# ProTrinket_doubleHPdisplay.net
KiCad netlist of a schematic drawn in EAGLE
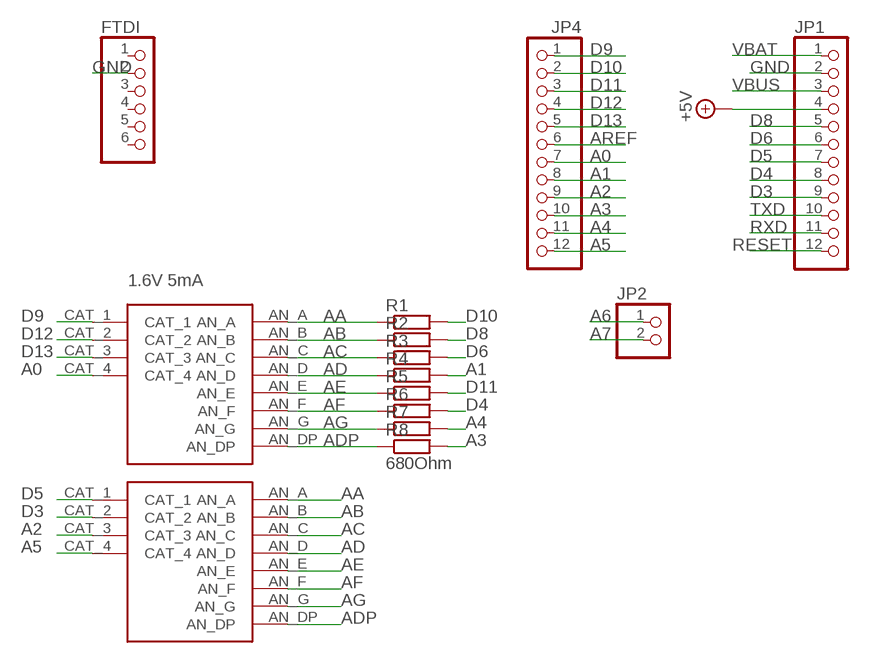
[diagram p0: schematic, sheet 1]

(export (version "E")
  (design (tool "Eeschema 10.0.6"))
  (components
    (comp (ref "FTDI")
      (value "PINHD-1X6CB")
      (footprint "eagle-import:1X06-CLEANBIG")
      (libsource (lib "eagle-import") (part "PINHD-1X6CB"))
    )
    (comp (ref "JP1")
      (value "PINHD-1X12-CB")
      (footprint "eagle-import:1X12-CB")
      (libsource (lib "eagle-import") (part "PINHD-1X12-CB"))
    )
    (comp (ref "JP2")
      (value "HEADER-1X2ROUND")
      (footprint "eagle-import:1X02_ROUND")
      (libsource (lib "eagle-import") (part "HEADER-1X2ROUND"))
    )
    (comp (ref "JP4")
      (value "PINHD-1X12-CB")
      (footprint "eagle-import:1X12-CB")
      (libsource (lib "eagle-import") (part "PINHD-1X12-CB"))
    )
    (comp (ref "R1")
      (value "R-EU_R0603")
      (footprint "eagle-import:R0603")
      (libsource (lib "eagle-import") (part "R-EU_R0603"))
    )
    (comp (ref "R2")
      (value "R-EU_R0603")
      (footprint "eagle-import:R0603")
      (libsource (lib "eagle-import") (part "R-EU_R0603"))
    )
    (comp (ref "R3")
      (value "R-EU_R0603")
      (footprint "eagle-import:R0603")
      (libsource (lib "eagle-import") (part "R-EU_R0603"))
    )
    (comp (ref "R4")
      (value "R-EU_R0603")
      (footprint "eagle-import:R0603")
      (libsource (lib "eagle-import") (part "R-EU_R0603"))
    )
    (comp (ref "R5")
      (value "R-EU_R0603")
      (footprint "eagle-import:R0603")
      (libsource (lib "eagle-import") (part "R-EU_R0603"))
    )
    (comp (ref "R6")
      (value "R-EU_R0603")
      (footprint "eagle-import:R0603")
      (libsource (lib "eagle-import") (part "R-EU_R0603"))
    )
    (comp (ref "R7")
      (value "R-EU_R0603")
      (footprint "eagle-import:R0603")
      (libsource (lib "eagle-import") (part "R-EU_R0603"))
    )
    (comp (ref "R8")
      (value "680Ohm")
      (footprint "eagle-import:R0603")
      (libsource (lib "eagle-import") (part "R-EU_R0603"))
    )
    (comp (ref "U$1")
      (value "QDSP-6064")
      (footprint "eagle-import:QDSP-6064")
      (libsource (lib "eagle-import") (part "QDSP-6064"))
    )
    (comp (ref "U$2")
      (value "QDSP-6064")
      (footprint "eagle-import:QDSP-6064")
      (libsource (lib "eagle-import") (part "QDSP-6064"))
    )
  )
  (nets
    (net (code "1") (name "+5V") (class "Default")
      (node (ref "JP1") (pin "4") (pinfunction "4_4") (pintype "passive"))
    )
    (net (code "2") (name "/A0") (class "Default")
      (node (ref "JP4") (pin "7") (pinfunction "7_7") (pintype "passive"))
      (node (ref "U$1") (pin "CAT_4") (pinfunction "CAT_4_CAT_4") (pintype "bidirectional"))
    )
    (net (code "3") (name "/A1") (class "Default")
      (node (ref "JP4") (pin "8") (pinfunction "8_8") (pintype "passive"))
      (node (ref "R4") (pin "2") (pinfunction "2_2") (pintype "passive"))
    )
    (net (code "4") (name "/A2") (class "Default")
      (node (ref "JP4") (pin "9") (pinfunction "9_9") (pintype "passive"))
      (node (ref "U$2") (pin "CAT_3") (pinfunction "CAT_3_CAT_3") (pintype "bidirectional"))
    )
    (net (code "5") (name "/A3") (class "Default")
      (node (ref "JP4") (pin "10") (pinfunction "10_10") (pintype "passive"))
      (node (ref "R8") (pin "2") (pinfunction "2_2") (pintype "passive"))
    )
    (net (code "6") (name "/A4") (class "Default")
      (node (ref "JP4") (pin "11") (pinfunction "11_11") (pintype "passive"))
      (node (ref "R7") (pin "2") (pinfunction "2_2") (pintype "passive"))
    )
    (net (code "7") (name "/A5") (class "Default")
      (node (ref "JP4") (pin "12") (pinfunction "12_12") (pintype "passive"))
      (node (ref "U$2") (pin "CAT_4") (pinfunction "CAT_4_CAT_4") (pintype "bidirectional"))
    )
    (net (code "8") (name "/A6") (class "Default")
      (node (ref "JP2") (pin "1") (pinfunction "1_1") (pintype "passive"))
    )
    (net (code "9") (name "/A7") (class "Default")
      (node (ref "JP2") (pin "2") (pinfunction "2_2") (pintype "passive"))
    )
    (net (code "10") (name "/AA") (class "Default")
      (node (ref "R1") (pin "1") (pinfunction "1_1") (pintype "passive"))
      (node (ref "U$1") (pin "AN_A") (pinfunction "AN_A_AN_A") (pintype "bidirectional"))
      (node (ref "U$2") (pin "AN_A") (pinfunction "AN_A_AN_A") (pintype "bidirectional"))
    )
    (net (code "11") (name "/AB") (class "Default")
      (node (ref "R2") (pin "1") (pinfunction "1_1") (pintype "passive"))
      (node (ref "U$1") (pin "AN_B") (pinfunction "AN_B_AN_B") (pintype "bidirectional"))
      (node (ref "U$2") (pin "AN_B") (pinfunction "AN_B_AN_B") (pintype "bidirectional"))
    )
    (net (code "12") (name "/AC") (class "Default")
      (node (ref "R3") (pin "1") (pinfunction "1_1") (pintype "passive"))
      (node (ref "U$1") (pin "AN_C") (pinfunction "AN_C_AN_C") (pintype "bidirectional"))
      (node (ref "U$2") (pin "AN_C") (pinfunction "AN_C_AN_C") (pintype "bidirectional"))
    )
    (net (code "13") (name "/AD") (class "Default")
      (node (ref "R4") (pin "1") (pinfunction "1_1") (pintype "passive"))
      (node (ref "U$1") (pin "AN_D") (pinfunction "AN_D_AN_D") (pintype "bidirectional"))
      (node (ref "U$2") (pin "AN_D") (pinfunction "AN_D_AN_D") (pintype "bidirectional"))
    )
    (net (code "14") (name "/ADP") (class "Default")
      (node (ref "R8") (pin "1") (pinfunction "1_1") (pintype "passive"))
      (node (ref "U$1") (pin "AN_DP") (pinfunction "AN_DP_AN_DP") (pintype "bidirectional"))
      (node (ref "U$2") (pin "AN_DP") (pinfunction "AN_DP_AN_DP") (pintype "bidirectional"))
    )
    (net (code "15") (name "/AE") (class "Default")
      (node (ref "R5") (pin "1") (pinfunction "1_1") (pintype "passive"))
      (node (ref "U$1") (pin "AN_E") (pinfunction "AN_E_AN_E") (pintype "bidirectional"))
      (node (ref "U$2") (pin "AN_E") (pinfunction "AN_E_AN_E") (pintype "bidirectional"))
    )
    (net (code "16") (name "/AF") (class "Default")
      (node (ref "R6") (pin "1") (pinfunction "1_1") (pintype "passive"))
      (node (ref "U$1") (pin "AN_F") (pinfunction "AN_F_AN_F") (pintype "bidirectional"))
      (node (ref "U$2") (pin "AN_F") (pinfunction "AN_F_AN_F") (pintype "bidirectional"))
    )
    (net (code "17") (name "/AG") (class "Default")
      (node (ref "R7") (pin "1") (pinfunction "1_1") (pintype "passive"))
      (node (ref "U$1") (pin "AN_G") (pinfunction "AN_G_AN_G") (pintype "bidirectional"))
      (node (ref "U$2") (pin "AN_G") (pinfunction "AN_G_AN_G") (pintype "bidirectional"))
    )
    (net (code "18") (name "/AREF") (class "Default")
      (node (ref "JP4") (pin "6") (pinfunction "6_6") (pintype "passive"))
    )
    (net (code "19") (name "/D3") (class "Default")
      (node (ref "JP1") (pin "9") (pinfunction "9_9") (pintype "passive"))
      (node (ref "U$2") (pin "CAT_2") (pinfunction "CAT_2_CAT_2") (pintype "bidirectional"))
    )
    (net (code "20") (name "/D4") (class "Default")
      (node (ref "JP1") (pin "8") (pinfunction "8_8") (pintype "passive"))
      (node (ref "R6") (pin "2") (pinfunction "2_2") (pintype "passive"))
    )
    (net (code "21") (name "/D5") (class "Default")
      (node (ref "JP1") (pin "7") (pinfunction "7_7") (pintype "passive"))
      (node (ref "U$2") (pin "CAT_1") (pinfunction "CAT_1_CAT_1") (pintype "bidirectional"))
    )
    (net (code "22") (name "/D6") (class "Default")
      (node (ref "JP1") (pin "6") (pinfunction "6_6") (pintype "passive"))
      (node (ref "R3") (pin "2") (pinfunction "2_2") (pintype "passive"))
    )
    (net (code "23") (name "/D8") (class "Default")
      (node (ref "JP1") (pin "5") (pinfunction "5_5") (pintype "passive"))
      (node (ref "R2") (pin "2") (pinfunction "2_2") (pintype "passive"))
    )
    (net (code "24") (name "/D9") (class "Default")
      (node (ref "JP4") (pin "1") (pinfunction "1_1") (pintype "passive"))
      (node (ref "U$1") (pin "CAT_1") (pinfunction "CAT_1_CAT_1") (pintype "bidirectional"))
    )
    (net (code "25") (name "/D10") (class "Default")
      (node (ref "JP4") (pin "2") (pinfunction "2_2") (pintype "passive"))
      (node (ref "R1") (pin "2") (pinfunction "2_2") (pintype "passive"))
    )
    (net (code "26") (name "/D11") (class "Default")
      (node (ref "JP4") (pin "3") (pinfunction "3_3") (pintype "passive"))
      (node (ref "R5") (pin "2") (pinfunction "2_2") (pintype "passive"))
    )
    (net (code "27") (name "/D12") (class "Default")
      (node (ref "JP4") (pin "4") (pinfunction "4_4") (pintype "passive"))
      (node (ref "U$1") (pin "CAT_2") (pinfunction "CAT_2_CAT_2") (pintype "bidirectional"))
    )
    (net (code "28") (name "/D13") (class "Default")
      (node (ref "JP4") (pin "5") (pinfunction "5_5") (pintype "passive"))
      (node (ref "U$1") (pin "CAT_3") (pinfunction "CAT_3_CAT_3") (pintype "bidirectional"))
    )
    (net (code "29") (name "/GND") (class "Default")
      (node (ref "FTDI") (pin "2") (pinfunction "2_2") (pintype "passive"))
      (node (ref "JP1") (pin "2") (pinfunction "2_2") (pintype "passive"))
    )
    (net (code "30") (name "/RESET") (class "Default")
      (node (ref "JP1") (pin "12") (pinfunction "12_12") (pintype "passive"))
    )
    (net (code "31") (name "/RXD") (class "Default")
      (node (ref "JP1") (pin "11") (pinfunction "11_11") (pintype "passive"))
    )
    (net (code "32") (name "/TXD") (class "Default")
      (node (ref "JP1") (pin "10") (pinfunction "10_10") (pintype "passive"))
    )
    (net (code "33") (name "/VBAT") (class "Default")
      (node (ref "JP1") (pin "1") (pinfunction "1_1") (pintype "passive"))
    )
    (net (code "34") (name "/VBUS") (class "Default")
      (node (ref "JP1") (pin "3") (pinfunction "3_3") (pintype "passive"))
    )
    (net (code "35") (name "unconnected-(FTDI-Pad1)") (class "Default")
      (node (ref "FTDI") (pin "1") (pinfunction "1_1") (pintype "passive"))
    )
    (net (code "36") (name "unconnected-(FTDI-Pad3)") (class "Default")
      (node (ref "FTDI") (pin "3") (pinfunction "3_3") (pintype "passive"))
    )
    (net (code "37") (name "unconnected-(FTDI-Pad4)") (class "Default")
      (node (ref "FTDI") (pin "4") (pinfunction "4_4") (pintype "passive"))
    )
    (net (code "38") (name "unconnected-(FTDI-Pad5)") (class "Default")
      (node (ref "FTDI") (pin "5") (pinfunction "5_5") (pintype "passive"))
    )
    (net (code "39") (name "unconnected-(FTDI-Pad6)") (class "Default")
      (node (ref "FTDI") (pin "6") (pinfunction "6_6") (pintype "passive"))
    )
  )
)
